# PT100.net
KiCad netlist of a schematic drawn in Altium Designer
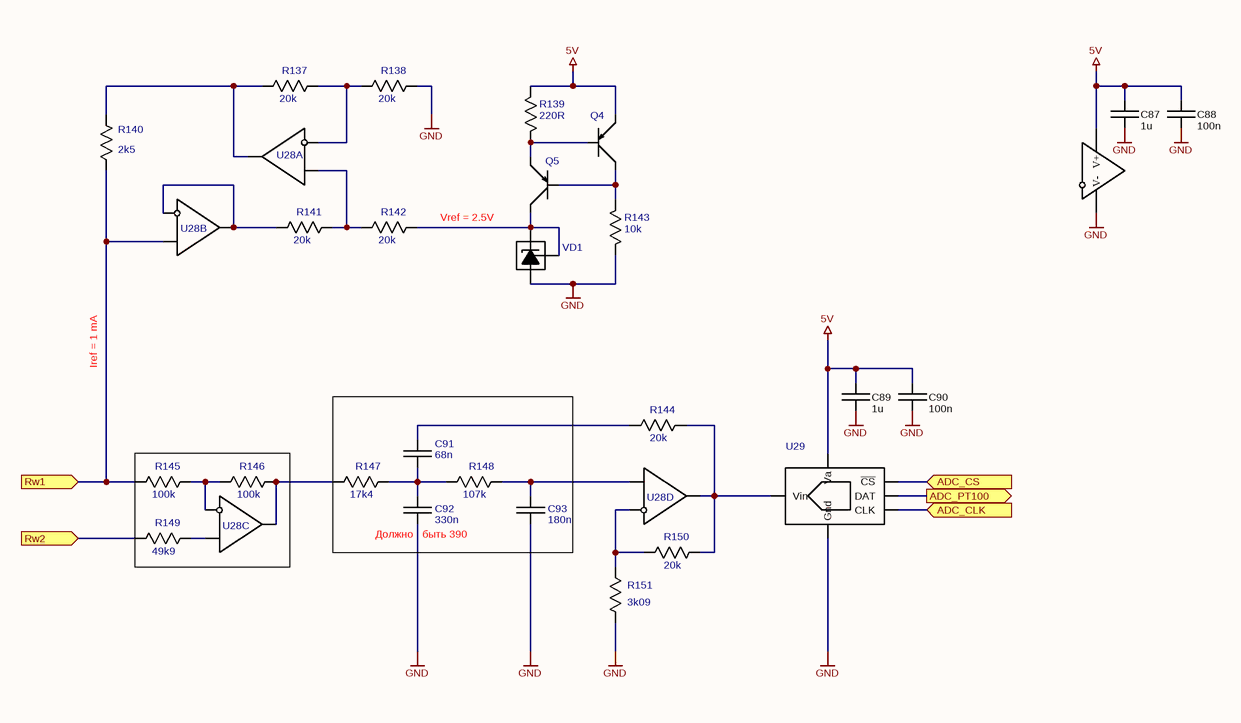
[diagram p0: PT100.SchDoc]

(export (version "E")
  (design (tool "Eeschema 10.0.6"))
  (components
    (comp (ref "C87")
      (value "1u")
      (footprint "CAP CER 0603 NP")
      (description "CC0603KRX5R7BB105")
      (libsource (lib "levin") (part "Capacitor"))
    )
    (comp (ref "C88")
      (value "100n")
      (footprint "CAP CER 0603 NP")
      (description "CC0603KRX7R9BB104")
      (libsource (lib "levin") (part "Capacitor"))
    )
    (comp (ref "C89")
      (value "1u")
      (footprint "CAP CER 0603 NP")
      (description "CC0603KRX5R7BB105")
      (libsource (lib "levin") (part "Capacitor"))
    )
    (comp (ref "C90")
      (value "100n")
      (footprint "CAP CER 0603 NP")
      (description "CC0603KRX7R9BB104")
      (libsource (lib "levin") (part "Capacitor"))
    )
    (comp (ref "C91")
      (value "68n")
      (footprint "CAP CER 0603 NP")
      (description "CC0603JRX7R9BB683")
      (libsource (lib "levin") (part "Capacitor"))
    )
    (comp (ref "C92")
      (value "330n")
      (footprint "CAP CER 0603 NP")
      (description "CC0603KRX5R8BB334")
      (libsource (lib "levin") (part "Capacitor"))
    )
    (comp (ref "C93")
      (value "180n")
      (footprint "CAP CER 0603 NP")
      (description "GRM188R71E184KA88D")
      (libsource (lib "levin") (part "Capacitor"))
    )
    (comp (ref "Q4")
      (value "PNP Bipolar Transistor")
      (footprint "SOT-23")
      (description "BC857")
      (libsource (lib "levin") (part "Bipolar PNP"))
    )
    (comp (ref "Q5")
      (value "PNP Bipolar Transistor")
      (footprint "SOT-23")
      (description "BC857")
      (libsource (lib "levin") (part "Bipolar PNP"))
    )
    (comp (ref "R137")
      (value "20k")
      (footprint "RES 0603")
      (description "RT0603BRD0720KL")
      (libsource (lib "levin") (part "Resistor"))
    )
    (comp (ref "R138")
      (value "20k")
      (footprint "RES 0603")
      (description "RT0603BRD0720KL")
      (libsource (lib "levin") (part "Resistor"))
    )
    (comp (ref "R139")
      (value "220R")
      (footprint "RES 0603")
      (description "RT0603BRD07220RL")
      (libsource (lib "levin") (part "Resistor"))
    )
    (comp (ref "R140")
      (value "2k5")
      (footprint "RES 0603")
      (description "AR03BTC2501")
      (libsource (lib "levin") (part "Resistor"))
    )
    (comp (ref "R141")
      (value "20k")
      (footprint "RES 0603")
      (description "RT0603BRD0720KL")
      (libsource (lib "levin") (part "Resistor"))
    )
    (comp (ref "R142")
      (value "20k")
      (footprint "RES 0603")
      (description "RT0603BRD0720KL")
      (libsource (lib "levin") (part "Resistor"))
    )
    (comp (ref "R143")
      (value "10k")
      (footprint "RES 0603")
      (description "RT0603BRD0710KL")
      (libsource (lib "levin") (part "Resistor"))
    )
    (comp (ref "R144")
      (value "20k")
      (footprint "RES 0603")
      (description "RC0603FR-0720KL")
      (libsource (lib "levin") (part "Resistor"))
    )
    (comp (ref "R145")
      (value "100k")
      (footprint "RES 0603")
      (description "RC0603FR-07100KL")
      (libsource (lib "levin") (part "Resistor"))
    )
    (comp (ref "R146")
      (value "100k")
      (footprint "RES 0603")
      (description "RC0603FR-07100KL")
      (libsource (lib "levin") (part "Resistor"))
    )
    (comp (ref "R147")
      (value "17k4")
      (footprint "RES 0603")
      (description "RC0603FR-0717K4L")
      (libsource (lib "levin") (part "Resistor"))
    )
    (comp (ref "R148")
      (value "107k")
      (footprint "RES 0603")
      (description "RC0603FR-07107KL")
      (libsource (lib "levin") (part "Resistor"))
    )
    (comp (ref "R149")
      (value "49k9")
      (footprint "RES 0603")
      (description "RC0603FR-0749K9L")
      (libsource (lib "levin") (part "Resistor"))
    )
    (comp (ref "R150")
      (value "20k")
      (footprint "RES 0603")
      (description "RC0603FR-0720KL")
      (libsource (lib "levin") (part "Resistor"))
    )
    (comp (ref "R151")
      (value "3k09")
      (footprint "RES 0603")
      (description "RC0603FR-073K09L")
      (libsource (lib "levin") (part "Resistor"))
    )
    (comp (ref "U28")
      (value "OpAmp x4 Small")
      (footprint "SOIC-14")
      (description "LMV324IDT")
      (libsource (lib "levin") (part "OpAmp x4 Small"))
    )
    (comp (ref "U29")
      (value "SAR ADC")
      (footprint "SOT-23-6")
      (description "ADC121S021CIMF")
      (libsource (lib "levin") (part "ADC121"))
    )
    (comp (ref "VD1")
      (value "Zenner Diode Adjustable")
      (footprint "SOT-23")
      (description "TL431ACDBZR")
      (libsource (lib "levin") (part "TL431"))
    )
  )
  (nets
    (net (code "1") (name "/ADC_CLK") (class "Default")
      (node (ref "U29") (pin "4") (pinfunction "CLK_4") (pintype "passive"))
    )
    (net (code "2") (name "/ADC_CS") (class "Default")
      (node (ref "U29") (pin "6") (pinfunction "~{CS}_6") (pintype "passive"))
    )
    (net (code "3") (name "/ADC_PT100") (class "Default")
      (node (ref "U29") (pin "5") (pinfunction "DAT_5") (pintype "passive"))
    )
    (net (code "4") (name "/Rw1") (class "Default")
      (node (ref "R140") (pin "1") (pinfunction "1_1") (pintype "passive"))
      (node (ref "R145") (pin "1") (pinfunction "1_1") (pintype "passive"))
      (node (ref "U28") (pin "4") (pinfunction "+IN_4") (pintype "passive"))
    )
    (net (code "5") (name "/Rw2") (class "Default")
      (node (ref "R149") (pin "1") (pinfunction "1_1") (pintype "passive"))
    )
    (net (code "6") (name "5V") (class "Default")
      (node (ref "C87") (pin "1") (pinfunction "1_1") (pintype "passive"))
      (node (ref "C88") (pin "1") (pinfunction "1_1") (pintype "passive"))
      (node (ref "C89") (pin "1") (pinfunction "1_1") (pintype "passive"))
      (node (ref "C90") (pin "1") (pinfunction "1_1") (pintype "passive"))
      (node (ref "Q4") (pin "2") (pinfunction "E_2") (pintype "passive"))
      (node (ref "R139") (pin "2") (pinfunction "2_2") (pintype "passive"))
      (node (ref "U28") (pin "13") (pinfunction "V+_13") (pintype "passive"))
      (node (ref "U29") (pin "1") (pinfunction "Va_1") (pintype "passive"))
    )
    (net (code "7") (name "GND") (class "Default")
      (node (ref "C87") (pin "2") (pinfunction "2_2") (pintype "passive"))
      (node (ref "C88") (pin "2") (pinfunction "2_2") (pintype "passive"))
      (node (ref "C89") (pin "2") (pinfunction "2_2") (pintype "passive"))
      (node (ref "C90") (pin "2") (pinfunction "2_2") (pintype "passive"))
      (node (ref "C92") (pin "1") (pinfunction "1_1") (pintype "passive"))
      (node (ref "C93") (pin "1") (pinfunction "1_1") (pintype "passive"))
      (node (ref "R138") (pin "2") (pinfunction "2_2") (pintype "passive"))
      (node (ref "R143") (pin "1") (pinfunction "1_1") (pintype "passive"))
      (node (ref "R151") (pin "1") (pinfunction "1_1") (pintype "passive"))
      (node (ref "U28") (pin "14") (pinfunction "V-_14") (pintype "passive"))
      (node (ref "U29") (pin "2") (pinfunction "Gnd_2") (pintype "passive"))
      (node (ref "VD1") (pin "1") (pinfunction "A_1") (pintype "passive"))
    )
    (net (code "8") (name "Net-(C91-Pad1)") (class "Default")
      (node (ref "C91") (pin "1") (pinfunction "1_1") (pintype "passive"))
      (node (ref "C92") (pin "2") (pinfunction "2_2") (pintype "passive"))
      (node (ref "R147") (pin "2") (pinfunction "2_2") (pintype "passive"))
      (node (ref "R148") (pin "1") (pinfunction "1_1") (pintype "passive"))
    )
    (net (code "9") (name "Net-(C91-Pad2)") (class "Default")
      (node (ref "C91") (pin "2") (pinfunction "2_2") (pintype "passive"))
      (node (ref "R144") (pin "1") (pinfunction "1_1") (pintype "passive"))
    )
    (net (code "10") (name "Net-(Q4-B)") (class "Default")
      (node (ref "Q4") (pin "1") (pinfunction "B_1") (pintype "passive"))
      (node (ref "Q5") (pin "2") (pinfunction "E_2") (pintype "passive"))
      (node (ref "R139") (pin "1") (pinfunction "1_1") (pintype "passive"))
    )
    (net (code "11") (name "Net-(Q4-C)") (class "Default")
      (node (ref "Q4") (pin "3") (pinfunction "C_3") (pintype "passive"))
      (node (ref "Q5") (pin "1") (pinfunction "B_1") (pintype "passive"))
      (node (ref "R143") (pin "2") (pinfunction "2_2") (pintype "passive"))
    )
    (net (code "12") (name "Net-(Q5-C)") (class "Default")
      (node (ref "Q5") (pin "3") (pinfunction "C_3") (pintype "passive"))
      (node (ref "R142") (pin "2") (pinfunction "2_2") (pintype "passive"))
      (node (ref "VD1") (pin "2") (pinfunction "C_2") (pintype "passive"))
      (node (ref "VD1") (pin "3") (pinfunction "Ref_3") (pintype "passive"))
    )
    (net (code "13") (name "Net-(U28A-+IN1)") (class "Default")
      (node (ref "R141") (pin "2") (pinfunction "2_2") (pintype "passive"))
      (node (ref "R142") (pin "1") (pinfunction "1_1") (pintype "passive"))
      (node (ref "U28") (pin "1") (pinfunction "+IN1_1") (pintype "passive"))
    )
    (net (code "14") (name "Net-(U28A--IN1)") (class "Default")
      (node (ref "R137") (pin "2") (pinfunction "2_2") (pintype "passive"))
      (node (ref "R138") (pin "1") (pinfunction "1_1") (pintype "passive"))
      (node (ref "U28") (pin "2") (pinfunction "-IN1_2") (pintype "passive"))
    )
    (net (code "15") (name "Net-(U28A-OUT1)") (class "Default")
      (node (ref "R137") (pin "1") (pinfunction "1_1") (pintype "passive"))
      (node (ref "R140") (pin "2") (pinfunction "2_2") (pintype "passive"))
      (node (ref "U28") (pin "3") (pinfunction "OUT1_3") (pintype "passive"))
    )
    (net (code "16") (name "Net-(U28B--IN)") (class "Default")
      (node (ref "R141") (pin "1") (pinfunction "1_1") (pintype "passive"))
      (node (ref "U28") (pin "5") (pinfunction "-IN_5") (pintype "passive"))
      (node (ref "U28") (pin "6") (pinfunction "OUT_6") (pintype "passive"))
    )
    (net (code "17") (name "Net-(U28C-+IN)") (class "Default")
      (node (ref "R149") (pin "2") (pinfunction "2_2") (pintype "passive"))
      (node (ref "U28") (pin "7") (pinfunction "+IN_7") (pintype "passive"))
    )
    (net (code "18") (name "Net-(U28C--IN)") (class "Default")
      (node (ref "R145") (pin "2") (pinfunction "2_2") (pintype "passive"))
      (node (ref "R146") (pin "1") (pinfunction "1_1") (pintype "passive"))
      (node (ref "U28") (pin "8") (pinfunction "-IN_8") (pintype "passive"))
    )
    (net (code "19") (name "Net-(U28C-OUT)") (class "Default")
      (node (ref "R146") (pin "2") (pinfunction "2_2") (pintype "passive"))
      (node (ref "R147") (pin "1") (pinfunction "1_1") (pintype "passive"))
      (node (ref "U28") (pin "9") (pinfunction "OUT_9") (pintype "passive"))
    )
    (net (code "20") (name "Net-(U28D-+IN)") (class "Default")
      (node (ref "C93") (pin "2") (pinfunction "2_2") (pintype "passive"))
      (node (ref "R148") (pin "2") (pinfunction "2_2") (pintype "passive"))
      (node (ref "U28") (pin "10") (pinfunction "+IN_10") (pintype "passive"))
    )
    (net (code "21") (name "Net-(U28D--IN)") (class "Default")
      (node (ref "R150") (pin "1") (pinfunction "1_1") (pintype "passive"))
      (node (ref "R151") (pin "2") (pinfunction "2_2") (pintype "passive"))
      (node (ref "U28") (pin "11") (pinfunction "-IN_11") (pintype "passive"))
    )
    (net (code "22") (name "Net-(U28D-OUT)") (class "Default")
      (node (ref "R144") (pin "2") (pinfunction "2_2") (pintype "passive"))
      (node (ref "R150") (pin "2") (pinfunction "2_2") (pintype "passive"))
      (node (ref "U28") (pin "12") (pinfunction "OUT_12") (pintype "passive"))
      (node (ref "U29") (pin "3") (pinfunction "Vin_3") (pintype "passive"))
    )
  )
)
